# untitled.net
KiCad netlist of a schematic drawn in EAGLE
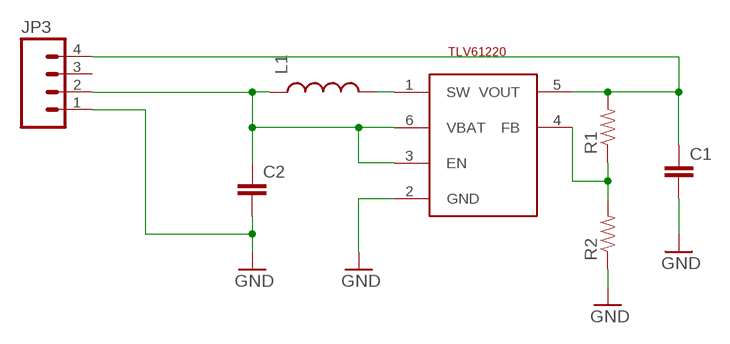
[diagram p0: schematic, sheet 1]

(export (version "E")
  (design (tool "Eeschema 10.0.6"))
  (components
    (comp (ref "C1")
      (value "CAP0805")
      (footprint "eagle-import:0805")
      (libsource (lib "eagle-import") (part "CAP0805"))
    )
    (comp (ref "C2")
      (value "CAP0805")
      (footprint "eagle-import:0805")
      (libsource (lib "eagle-import") (part "CAP0805"))
    )
    (comp (ref "JP3")
      (value "M04LOCK")
      (footprint "eagle-import:1X04_LOCK")
      (libsource (lib "eagle-import") (part "M04LOCK"))
    )
    (comp (ref "L1")
      (value "INDUCTOR0805")
      (footprint "eagle-import:0805")
      (libsource (lib "eagle-import") (part "INDUCTOR0805"))
    )
    (comp (ref "R1")
      (value "RESISTOR0805-RES")
      (footprint "eagle-import:0805")
      (libsource (lib "eagle-import") (part "RESISTOR0805-RES"))
    )
    (comp (ref "R2")
      (value "RESISTOR0805-RES")
      (footprint "eagle-import:0805")
      (libsource (lib "eagle-import") (part "RESISTOR0805-RES"))
    )
    (comp (ref "U$1")
      (value "TLV61220")
      (footprint "eagle-import:SOT23-6L")
      (libsource (lib "eagle-import") (part "TI-TLV61220"))
    )
  )
  (nets
    (net (code "1") (name "GND") (class "Default")
      (node (ref "C1") (pin "2") (pinfunction "2_2") (pintype "passive"))
      (node (ref "C2") (pin "2") (pinfunction "2_2") (pintype "passive"))
      (node (ref "JP3") (pin "1") (pinfunction "1_1") (pintype "passive"))
      (node (ref "R2") (pin "1") (pinfunction "1_1") (pintype "passive"))
      (node (ref "U$1") (pin "2") (pinfunction "GND_2") (pintype "power_in"))
    )
    (net (code "2") (name "Net-(U$1-EN)") (class "Default")
      (node (ref "C2") (pin "1") (pinfunction "1_1") (pintype "passive"))
      (node (ref "JP3") (pin "2") (pinfunction "2_2") (pintype "passive"))
      (node (ref "L1") (pin "1") (pinfunction "1_1") (pintype "passive"))
      (node (ref "U$1") (pin "3") (pinfunction "EN_3") (pintype "input"))
      (node (ref "U$1") (pin "6") (pinfunction "VBAT_6") (pintype "power_in"))
    )
    (net (code "3") (name "Net-(U$1-FB)") (class "Default")
      (node (ref "R1") (pin "1") (pinfunction "1_1") (pintype "passive"))
      (node (ref "R2") (pin "2") (pinfunction "2_2") (pintype "passive"))
      (node (ref "U$1") (pin "4") (pinfunction "FB_4") (pintype "input"))
    )
    (net (code "4") (name "Net-(U$1-SW)") (class "Default")
      (node (ref "L1") (pin "2") (pinfunction "2_2") (pintype "passive"))
      (node (ref "U$1") (pin "1") (pinfunction "SW_1") (pintype "power_in"))
    )
    (net (code "5") (name "Net-(U$1-VOUT)") (class "Default")
      (node (ref "C1") (pin "1") (pinfunction "1_1") (pintype "passive"))
      (node (ref "JP3") (pin "4") (pinfunction "4_4") (pintype "passive"))
      (node (ref "R1") (pin "2") (pinfunction "2_2") (pintype "passive"))
      (node (ref "U$1") (pin "5") (pinfunction "VOUT_5") (pintype "power_in"))
    )
    (net (code "6") (name "unconnected-(JP3-Pad3)") (class "Default")
      (node (ref "JP3") (pin "3") (pinfunction "3_3") (pintype "passive"))
    )
  )
)
